# WiFi_Lock.net
KiCad netlist of a schematic drawn in Altium Designer
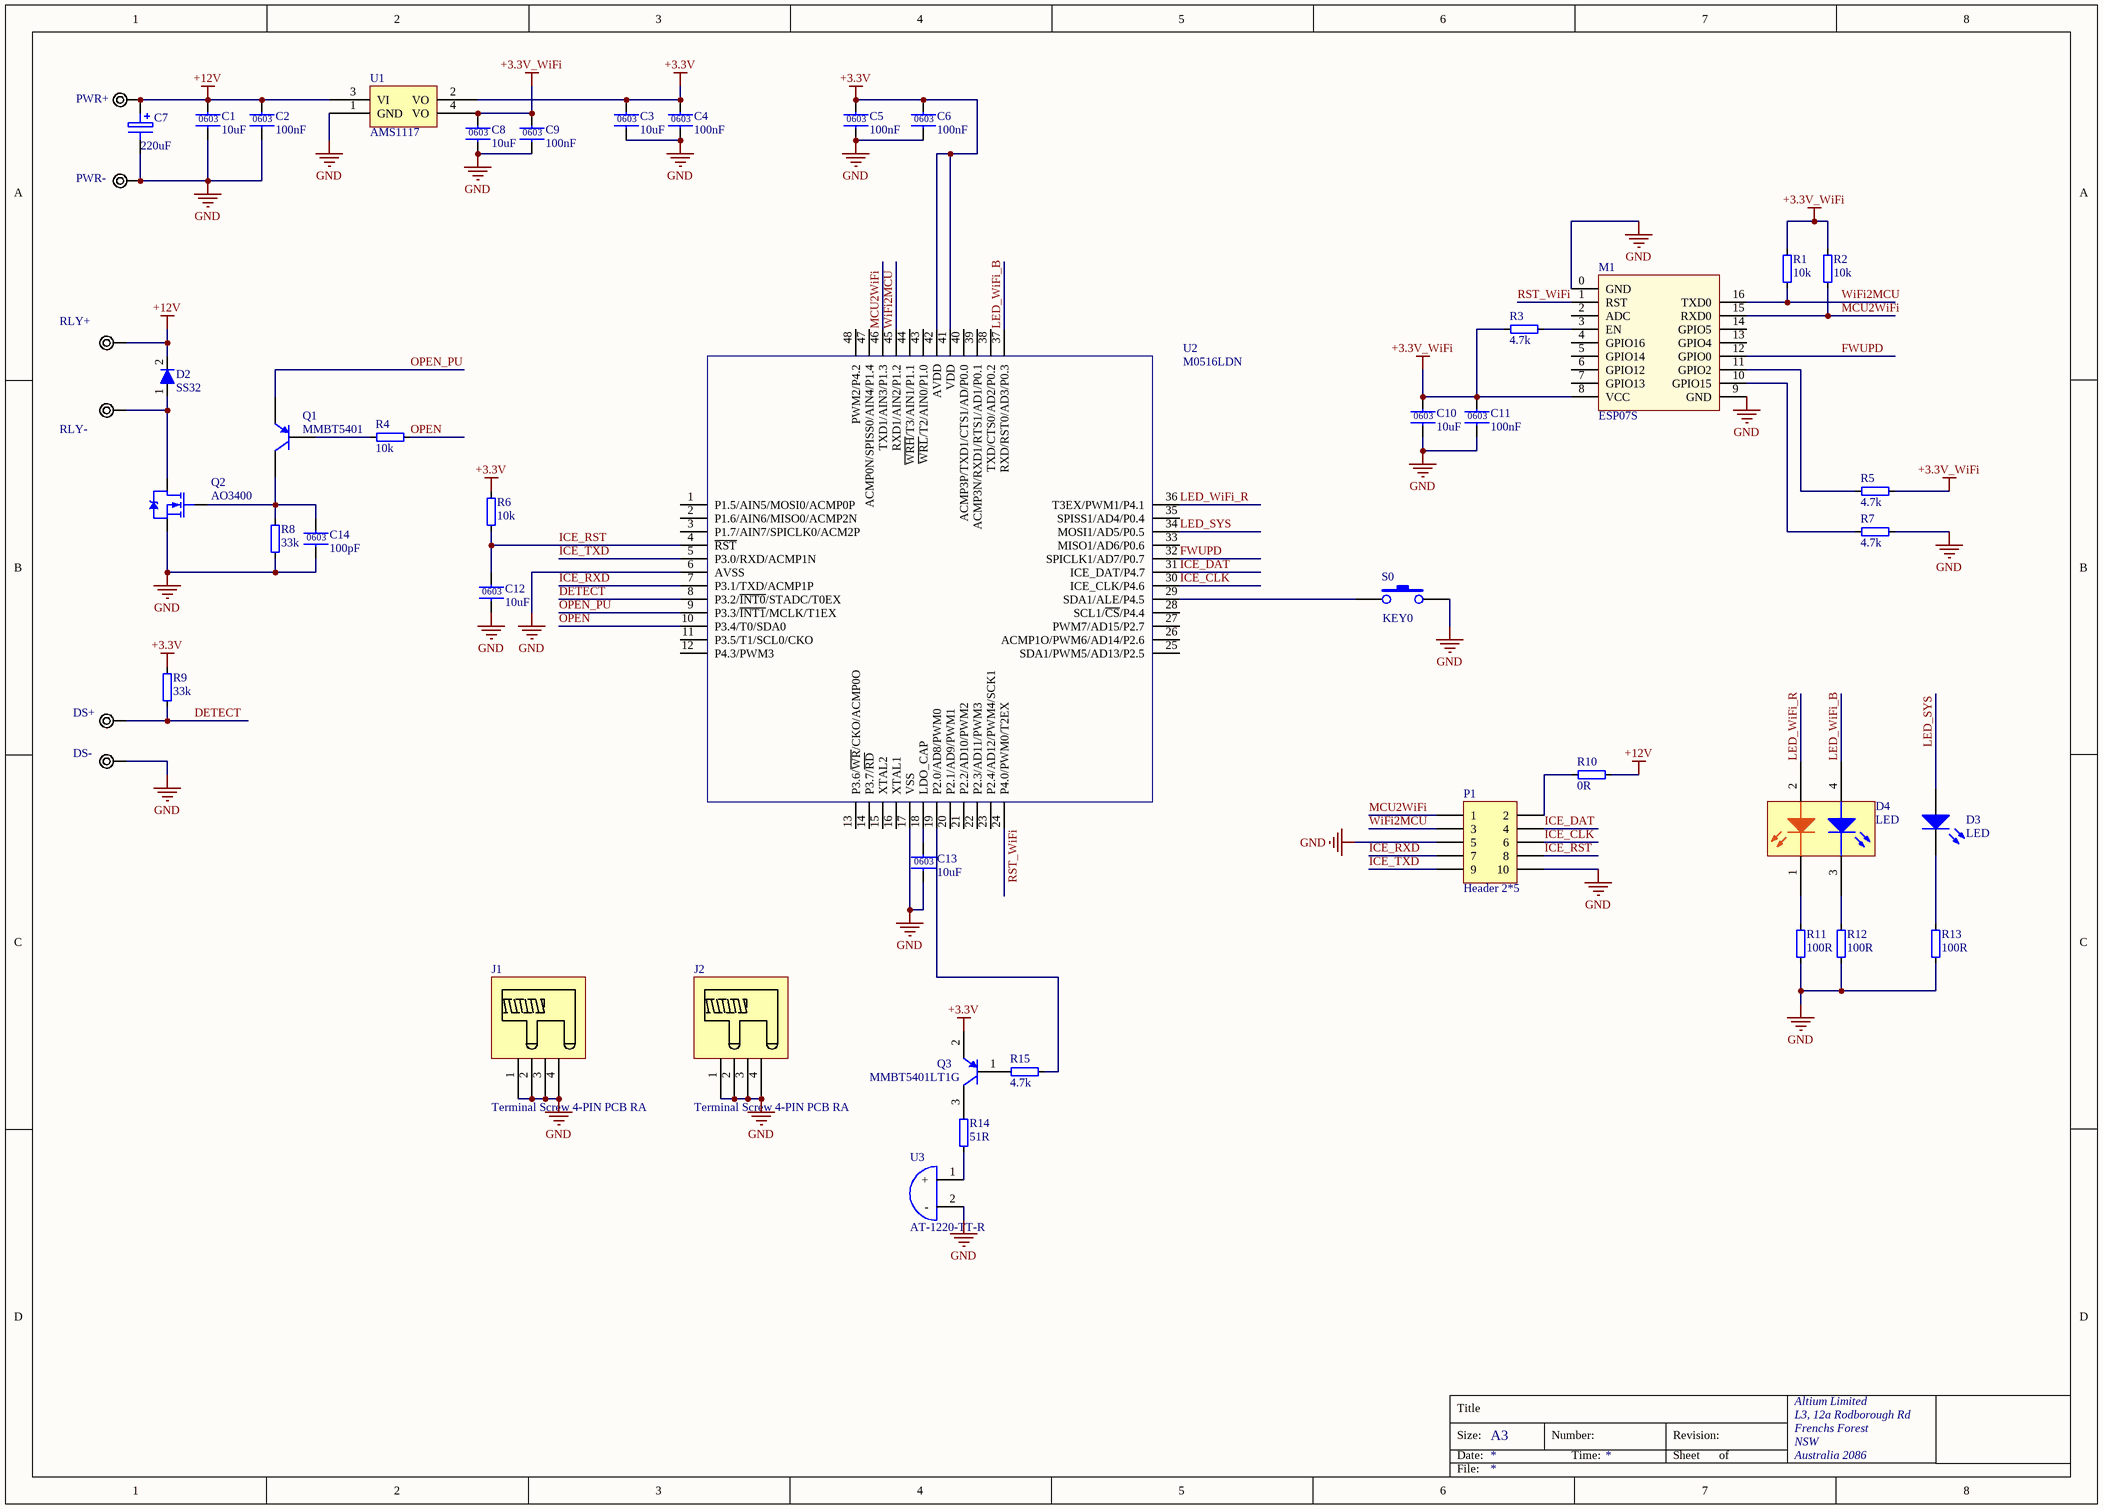
[diagram p0: WiFi_Lock.SchDoc]

(export (version "E")
  (design (tool "Eeschema 10.0.6"))
  (components
    (comp (ref "C1")
      (value "10uF")
      (footprint "0603")
      (description "CAP0603")
      (libsource (lib "AltiumDesignerIntLib") (part "CAP0603"))
    )
    (comp (ref "C2")
      (value "100nF")
      (footprint "0603")
      (description "CAP0603")
      (libsource (lib "AltiumDesignerIntLib") (part "CAP0603"))
    )
    (comp (ref "C3")
      (value "10uF")
      (footprint "0603")
      (description "CAP0603")
      (libsource (lib "AltiumDesignerIntLib") (part "CAP0603"))
    )
    (comp (ref "C4")
      (value "100nF")
      (footprint "0603")
      (description "CAP0603")
      (libsource (lib "AltiumDesignerIntLib") (part "CAP0603"))
    )
    (comp (ref "C5")
      (value "100nF")
      (footprint "0603")
      (description "CAP0603")
      (libsource (lib "AltiumDesignerIntLib") (part "CAP0603"))
    )
    (comp (ref "C6")
      (value "100nF")
      (footprint "0603")
      (description "CAP0603")
      (libsource (lib "AltiumDesignerIntLib") (part "CAP0603"))
    )
    (comp (ref "C7")
      (value "220uF")
      (footprint "SMD-EC-F6.3")
      (description "220μF 16V Aluminum Electrolytic Capacitors Radial, Can - SMD 160 mohm @ 100kHz 2000 Hrs @ 105°C")
      (fields
        (field (name "MANUFACTURER") "Panasonic Electronic Components")
        (field (name "PARTNUMBER") "EEE-FPC221XAP")
      )
      (libsource (lib "Panasonic Aluminum Electrolytic Capacitors (Surface Mount Type)") (part "EEE-FPC221XAP"))
    )
    (comp (ref "C8")
      (value "10uF")
      (footprint "0603")
      (description "CAP0603")
      (libsource (lib "AltiumDesignerIntLib") (part "CAP0603"))
    )
    (comp (ref "C9")
      (value "100nF")
      (footprint "0603")
      (description "CAP0603")
      (libsource (lib "AltiumDesignerIntLib") (part "CAP0603"))
    )
    (comp (ref "C10")
      (value "10uF")
      (footprint "0603")
      (description "CAP0603")
      (libsource (lib "AltiumDesignerIntLib") (part "CAP0603"))
    )
    (comp (ref "C11")
      (value "100nF")
      (footprint "0603")
      (description "CAP0603")
      (libsource (lib "AltiumDesignerIntLib") (part "CAP0603"))
    )
    (comp (ref "C12")
      (value "10uF")
      (footprint "0603")
      (description "CAP0603")
      (libsource (lib "AltiumDesignerIntLib") (part "CAP0603"))
    )
    (comp (ref "C13")
      (value "10uF")
      (footprint "0603")
      (description "CAP0603")
      (libsource (lib "AltiumDesignerIntLib") (part "CAP0603"))
    )
    (comp (ref "C14")
      (value "100pF")
      (footprint "0603")
      (description "CAP0603")
      (libsource (lib "AltiumDesignerIntLib") (part "CAP0603"))
    )
    (comp (ref "D2")
      (value "SS32")
      (footprint "DO-214AC")
      (libsource (lib "AltiumDesignerIntLib") (part "Diode"))
    )
    (comp (ref "D3")
      (value "LED")
      (footprint "0603")
      (description "Typical INFRARED GaAs LED")
      (fields (field (name "PUBLISHER") "Altium Limited"))
      (libsource (lib "AltiumDesignerIntLib") (part "LED"))
    )
    (comp (ref "D4")
      (value "LED")
      (footprint "DLED2.00x1.25mm")
      (description "Red & Blue")
      (libsource (lib "AltiumDesignerIntLib") (part "LED-RB"))
    )
    (comp (ref "J1")
      (value "Terminal Screw 4-PIN PCB RA")
      (footprint "TERMSCREW4-B11.5X8.5X7.8mm/T5.0X7.5mm/RA")
      (description "Terminal Screw 4-PIN, Thru Hole, PCB Right Angle")
      (libsource (lib "AltiumDesignerIntLib") (part "Terminal Screw 4-PIN PCB RA"))
    )
    (comp (ref "J2")
      (value "Terminal Screw 4-PIN PCB RA")
      (footprint "TERMSCREW4-B11.5X8.5X7.8mm/T5.0X7.5mm/RA")
      (description "Terminal Screw 4-PIN, Thru Hole, PCB Right Angle")
      (libsource (lib "AltiumDesignerIntLib") (part "Terminal Screw 4-PIN PCB RA"))
    )
    (comp (ref "M1")
      (value "ESP07S")
      (footprint "ESP-07S Module")
      (description "ESP-07S Wi-Fi Module")
      (libsource (lib "AltiumDesignerIntLib") (part "ESP-07S Module"))
    )
    (comp (ref "P1")
      (value "Header 2*5")
      (footprint "HDR2X5T0.1")
      (description "Header, 2-Pin, Dual row")
      (fields (field (name "PUBLISHER") "Altium Limited"))
      (libsource (lib "AltiumDesignerIntLib") (part "Header 2*5"))
    )
    (comp (ref "PAD1")
      (value "PWR+")
      (footprint "PAD-MUL-ROUND-D1.5H0.6")
      (description "Probe, Test Point")
      (libsource (lib "AltiumDesignerIntLib") (part "PAD"))
    )
    (comp (ref "PAD2")
      (value "PWR-")
      (footprint "PAD-MUL-ROUND-D1.5H0.6")
      (description "Probe, Test Point")
      (libsource (lib "AltiumDesignerIntLib") (part "PAD"))
    )
    (comp (ref "PAD3")
      (value "RLY+")
      (footprint "PAD-MUL-ROUND-D1.5H0.6")
      (description "Probe, Test Point")
      (libsource (lib "AltiumDesignerIntLib") (part "PAD"))
    )
    (comp (ref "PAD4")
      (value "RLY-")
      (footprint "PAD-MUL-ROUND-D1.5H0.6")
      (description "Probe, Test Point")
      (libsource (lib "AltiumDesignerIntLib") (part "PAD"))
    )
    (comp (ref "PAD5")
      (value "DS+")
      (footprint "PAD-MUL-ROUND-D1.5H0.6")
      (description "Probe, Test Point")
      (libsource (lib "AltiumDesignerIntLib") (part "PAD"))
    )
    (comp (ref "PAD6")
      (value "DS-")
      (footprint "PAD-MUL-ROUND-D1.5H0.6")
      (description "Probe, Test Point")
      (libsource (lib "AltiumDesignerIntLib") (part "PAD"))
    )
    (comp (ref "Q1")
      (value "MMBT5401")
      (footprint "SOT95P230X110-3N")
      (description "PNP General Purpose Amplifier")
      (libsource (lib "AltiumDesignerIntLib") (part "MMBT5401"))
    )
    (comp (ref "Q2")
      (value "AO3400")
      (footprint "SOT95P230X110-3N")
      (description "30V 5.8A N-Channel MOSFET, MAX VGS = 1.45V")
      (libsource (lib "AltiumDesignerIntLib") (part "AO3400"))
    )
    (comp (ref "Q3")
      (value "MMBT5401LT1G")
      (footprint "ONSC-SOT-23-3-318-08_V")
      (description "High Voltage Transistor, PNP Silicon, 3-Pin SOT-23, Pb-Free, Tape and Reel")
      (fields (field (name "MANUFACTURER") "On Semiconductor"))
      (libsource (lib "ON Semi General Purpose Transistors") (part "MMBT5401LT1G"))
    )
    (comp (ref "R1") (value "10k") (footprint "0603") (libsource (lib "AltiumDesignerIntLib") (part "RES")))
    (comp (ref "R2") (value "10k") (footprint "0603") (libsource (lib "AltiumDesignerIntLib") (part "RES")))
    (comp (ref "R3") (value "4.7k") (footprint "0603") (libsource (lib "AltiumDesignerIntLib") (part "RES")))
    (comp (ref "R4") (value "10k") (footprint "0603") (libsource (lib "AltiumDesignerIntLib") (part "RES")))
    (comp (ref "R5") (value "4.7k") (footprint "0603") (libsource (lib "AltiumDesignerIntLib") (part "RES")))
    (comp (ref "R6") (value "10k") (footprint "0603") (libsource (lib "AltiumDesignerIntLib") (part "RES")))
    (comp (ref "R7") (value "4.7k") (footprint "0603") (libsource (lib "AltiumDesignerIntLib") (part "RES")))
    (comp (ref "R8") (value "33k") (footprint "0603") (libsource (lib "AltiumDesignerIntLib") (part "RES")))
    (comp (ref "R9") (value "33k") (footprint "0603") (libsource (lib "AltiumDesignerIntLib") (part "RES")))
    (comp (ref "R10") (value "0R") (footprint "0603") (libsource (lib "AltiumDesignerIntLib") (part "RES")))
    (comp (ref "R11") (value "100R") (footprint "0603") (libsource (lib "AltiumDesignerIntLib") (part "RES")))
    (comp (ref "R12") (value "100R") (footprint "0603") (libsource (lib "AltiumDesignerIntLib") (part "RES")))
    (comp (ref "R13") (value "100R") (footprint "0603") (libsource (lib "AltiumDesignerIntLib") (part "RES")))
    (comp (ref "R14") (value "51R") (footprint "0603") (libsource (lib "AltiumDesignerIntLib") (part "RES")))
    (comp (ref "R15") (value "4.7k") (footprint "0603") (libsource (lib "AltiumDesignerIntLib") (part "RES")))
    (comp (ref "S0")
      (value "KEY0")
      (footprint "SW6.00x3.00mm")
      (description "Top push Switch")
      (libsource (lib "AltiumDesignerIntLib") (part "SW-TACT"))
    )
    (comp (ref "U1")
      (value "AMS1117")
      (footprint "SOT-223")
      (description "三端线性稳压")
      (libsource (lib "AltiumDesignerIntLib") (part "AMS1117"))
    )
    (comp (ref "U2")
      (value "M0516LDN")
      (footprint "LQFP-48")
      (description "ARM Cortex -M0 32-bit Microcontroller")
      (libsource (lib "AltiumDesignerIntLib") (part "M0516LDN"))
    )
    (comp (ref "U3")
      (value "AT-1220-TT-R")
      (footprint "Transducer_12mm(D)x8.5mm(H)_6.5mm(P)")
      (fields (field (name "MANUFACTURER") "PUI Audio Inc."))
      (libsource (lib "PUI Audio Transducers") (part "AT-1220-TT-R"))
    )
  )
  (nets
    (net (code "1") (name "+3.3V") (class "Default")
      (node (ref "C3") (pin "1") (pinfunction "1_1") (pintype "passive"))
      (node (ref "C4") (pin "1") (pinfunction "1_1") (pintype "passive"))
      (node (ref "C5") (pin "1") (pinfunction "1_1") (pintype "passive"))
      (node (ref "C6") (pin "1") (pinfunction "1_1") (pintype "passive"))
      (node (ref "Q3") (pin "2") (pinfunction "E_2") (pintype "passive"))
      (node (ref "R6") (pin "1") (pinfunction "1_1") (pintype "passive"))
      (node (ref "R9") (pin "2") (pinfunction "2_2") (pintype "passive"))
      (node (ref "U1") (pin "2") (pinfunction "VO_2") (pintype "passive"))
      (node (ref "U2") (pin "41") (pinfunction "VDD_41") (pintype "passive"))
      (node (ref "U2") (pin "42") (pinfunction "AVDD_42") (pintype "passive"))
    )
    (net (code "2") (name "+3.3V_WiFi") (class "Default")
      (node (ref "C10") (pin "1") (pinfunction "1_1") (pintype "passive"))
      (node (ref "C11") (pin "1") (pinfunction "1_1") (pintype "passive"))
      (node (ref "C8") (pin "1") (pinfunction "1_1") (pintype "passive"))
      (node (ref "C9") (pin "1") (pinfunction "1_1") (pintype "passive"))
      (node (ref "M1") (pin "8") (pinfunction "VCC_8") (pintype "passive"))
      (node (ref "R1") (pin "2") (pinfunction "2_2") (pintype "passive"))
      (node (ref "R2") (pin "2") (pinfunction "2_2") (pintype "passive"))
      (node (ref "R3") (pin "1") (pinfunction "1_1") (pintype "passive"))
      (node (ref "R5") (pin "2") (pinfunction "2_2") (pintype "passive"))
      (node (ref "U1") (pin "4") (pinfunction "VO_4") (pintype "passive"))
    )
    (net (code "3") (name "+12V") (class "Default")
      (node (ref "C1") (pin "1") (pinfunction "1_1") (pintype "passive"))
      (node (ref "C2") (pin "1") (pinfunction "1_1") (pintype "passive"))
      (node (ref "C7") (pin "1") (pinfunction "1_1") (pintype "passive"))
      (node (ref "D2") (pin "2") (pinfunction "K_2") (pintype "passive"))
      (node (ref "PAD1") (pin "1") (pinfunction "1_1") (pintype "passive"))
      (node (ref "PAD3") (pin "1") (pinfunction "1_1") (pintype "passive"))
      (node (ref "R10") (pin "2") (pinfunction "2_2") (pintype "passive"))
      (node (ref "U1") (pin "3") (pinfunction "VI_3") (pintype "passive"))
    )
    (net (code "4") (name "/DETECT") (class "Default")
      (node (ref "PAD5") (pin "1") (pinfunction "1_1") (pintype "passive"))
      (node (ref "R9") (pin "1") (pinfunction "1_1") (pintype "passive"))
      (node (ref "U2") (pin "8") (pinfunction "P3.2/~{INT0}/STADC/T0EX_8") (pintype "passive"))
    )
    (net (code "5") (name "/FWUPD") (class "Default")
      (node (ref "M1") (pin "12") (pinfunction "GPIO0_12") (pintype "passive"))
      (node (ref "U2") (pin "32") (pinfunction "SPICLK1/AD7/P0.7_32") (pintype "passive"))
    )
    (net (code "6") (name "/ICE_CLK") (class "Default")
      (node (ref "P1") (pin "6") (pinfunction "6_6") (pintype "passive"))
      (node (ref "U2") (pin "30") (pinfunction "ICE_CLK/P4.6_30") (pintype "passive"))
    )
    (net (code "7") (name "/ICE_DAT") (class "Default")
      (node (ref "P1") (pin "4") (pinfunction "4_4") (pintype "passive"))
      (node (ref "U2") (pin "31") (pinfunction "ICE_DAT/P4.7_31") (pintype "passive"))
    )
    (net (code "8") (name "/ICE_RST") (class "Default")
      (node (ref "C12") (pin "1") (pinfunction "1_1") (pintype "passive"))
      (node (ref "P1") (pin "8") (pinfunction "8_8") (pintype "passive"))
      (node (ref "R6") (pin "2") (pinfunction "2_2") (pintype "passive"))
      (node (ref "U2") (pin "4") (pinfunction "~{RST}_4") (pintype "passive"))
    )
    (net (code "9") (name "/ICE_RXD") (class "Default")
      (node (ref "P1") (pin "7") (pinfunction "7_7") (pintype "passive"))
      (node (ref "U2") (pin "7") (pinfunction "P3.1/TXD/ACMP1P_7") (pintype "passive"))
    )
    (net (code "10") (name "/ICE_TXD") (class "Default")
      (node (ref "P1") (pin "9") (pinfunction "9_9") (pintype "passive"))
      (node (ref "U2") (pin "5") (pinfunction "P3.0/RXD/ACMP1N_5") (pintype "passive"))
    )
    (net (code "11") (name "/LED_SYS") (class "Default")
      (node (ref "D3") (pin "1") (pinfunction "A_1") (pintype "passive"))
      (node (ref "U2") (pin "34") (pinfunction "MOSI1/AD5/P0.5_34") (pintype "passive"))
    )
    (net (code "12") (name "/LED_WiFi_B") (class "Default")
      (node (ref "D4") (pin "4") (pinfunction "BA_4") (pintype "passive"))
      (node (ref "U2") (pin "37") (pinfunction "RXD/RST0/AD3/P0.3_37") (pintype "passive"))
    )
    (net (code "13") (name "/LED_WiFi_R") (class "Default")
      (node (ref "D4") (pin "2") (pinfunction "RA_2") (pintype "passive"))
      (node (ref "U2") (pin "36") (pinfunction "T3EX/PWM1/P4.1_36") (pintype "passive"))
    )
    (net (code "14") (name "/MCU2WiFi") (class "Default")
      (node (ref "M1") (pin "15") (pinfunction "RXD0_15") (pintype "passive"))
      (node (ref "P1") (pin "1") (pinfunction "1_1") (pintype "passive"))
      (node (ref "R2") (pin "1") (pinfunction "1_1") (pintype "passive"))
      (node (ref "U2") (pin "46") (pinfunction "TXD1/AIN3/P1.3_46") (pintype "passive"))
    )
    (net (code "15") (name "/OPEN") (class "Default")
      (node (ref "R4") (pin "1") (pinfunction "1_1") (pintype "passive"))
      (node (ref "U2") (pin "10") (pinfunction "P3.4/T0/SDA0_10") (pintype "passive"))
    )
    (net (code "16") (name "/OPEN_PU") (class "Default")
      (node (ref "Q1") (pin "2") (pinfunction "E_2") (pintype "passive"))
      (node (ref "U2") (pin "9") (pinfunction "P3.3/~{INT1}/MCLK/T1EX_9") (pintype "passive"))
    )
    (net (code "17") (name "/RST_WiFi") (class "Default")
      (node (ref "M1") (pin "1") (pinfunction "RST_1") (pintype "passive"))
      (node (ref "U2") (pin "24") (pinfunction "P4.0/PWM0/T2EX_24") (pintype "passive"))
    )
    (net (code "18") (name "/WiFi2MCU") (class "Default")
      (node (ref "M1") (pin "16") (pinfunction "TXD0_16") (pintype "passive"))
      (node (ref "P1") (pin "3") (pinfunction "3_3") (pintype "passive"))
      (node (ref "R1") (pin "1") (pinfunction "1_1") (pintype "passive"))
      (node (ref "U2") (pin "45") (pinfunction "RXD1/AIN2/P1.2_45") (pintype "passive"))
    )
    (net (code "19") (name "GND") (class "Default")
      (node (ref "C1") (pin "2") (pinfunction "2_2") (pintype "passive"))
      (node (ref "C10") (pin "2") (pinfunction "2_2") (pintype "passive"))
      (node (ref "C11") (pin "2") (pinfunction "2_2") (pintype "passive"))
      (node (ref "C12") (pin "2") (pinfunction "2_2") (pintype "passive"))
      (node (ref "C13") (pin "2") (pinfunction "2_2") (pintype "passive"))
      (node (ref "C14") (pin "2") (pinfunction "2_2") (pintype "passive"))
      (node (ref "C2") (pin "2") (pinfunction "2_2") (pintype "passive"))
      (node (ref "C3") (pin "2") (pinfunction "2_2") (pintype "passive"))
      (node (ref "C4") (pin "2") (pinfunction "2_2") (pintype "passive"))
      (node (ref "C5") (pin "2") (pinfunction "2_2") (pintype "passive"))
      (node (ref "C6") (pin "2") (pinfunction "2_2") (pintype "passive"))
      (node (ref "C7") (pin "2") (pinfunction "2_2") (pintype "passive"))
      (node (ref "C8") (pin "2") (pinfunction "2_2") (pintype "passive"))
      (node (ref "C9") (pin "2") (pinfunction "2_2") (pintype "passive"))
      (node (ref "J1") (pin "1") (pintype "passive"))
      (node (ref "J1") (pin "2") (pintype "passive"))
      (node (ref "J1") (pin "3") (pintype "passive"))
      (node (ref "J1") (pin "4") (pintype "passive"))
      (node (ref "J2") (pin "1") (pintype "passive"))
      (node (ref "J2") (pin "2") (pintype "passive"))
      (node (ref "J2") (pin "3") (pintype "passive"))
      (node (ref "J2") (pin "4") (pintype "passive"))
      (node (ref "M1") (pin "0") (pinfunction "GND_0") (pintype "passive"))
      (node (ref "M1") (pin "9") (pinfunction "GND_9") (pintype "passive"))
      (node (ref "P1") (pin "10") (pinfunction "10_10") (pintype "passive"))
      (node (ref "P1") (pin "5") (pinfunction "5_5") (pintype "passive"))
      (node (ref "PAD2") (pin "1") (pinfunction "1_1") (pintype "passive"))
      (node (ref "PAD6") (pin "1") (pinfunction "1_1") (pintype "passive"))
      (node (ref "Q2") (pin "2") (pinfunction "S_2") (pintype "passive"))
      (node (ref "R11") (pin "1") (pinfunction "1_1") (pintype "passive"))
      (node (ref "R12") (pin "1") (pinfunction "1_1") (pintype "passive"))
      (node (ref "R13") (pin "1") (pinfunction "1_1") (pintype "passive"))
      (node (ref "R7") (pin "2") (pinfunction "2_2") (pintype "passive"))
      (node (ref "R8") (pin "1") (pinfunction "1_1") (pintype "passive"))
      (node (ref "S0") (pin "2") (pinfunction "2_2") (pintype "passive"))
      (node (ref "U1") (pin "1") (pinfunction "GND_1") (pintype "passive"))
      (node (ref "U2") (pin "17") (pinfunction "VSS_17") (pintype "passive"))
      (node (ref "U2") (pin "6") (pinfunction "AVSS_6") (pintype "passive"))
      (node (ref "U3") (pin "2") (pinfunction "-_2") (pintype "passive"))
    )
    (net (code "20") (name "Net-(D2-A)") (class "Default")
      (node (ref "D2") (pin "1") (pinfunction "A_1") (pintype "passive"))
      (node (ref "PAD4") (pin "1") (pinfunction "1_1") (pintype "passive"))
      (node (ref "Q2") (pin "3") (pinfunction "D_3") (pintype "passive"))
    )
    (net (code "21") (name "Net-(D3-K)") (class "Default")
      (node (ref "D3") (pin "2") (pinfunction "K_2") (pintype "passive"))
      (node (ref "R13") (pin "2") (pinfunction "2_2") (pintype "passive"))
    )
    (net (code "22") (name "Net-(D4-BK)") (class "Default")
      (node (ref "D4") (pin "3") (pinfunction "BK_3") (pintype "passive"))
      (node (ref "R12") (pin "2") (pinfunction "2_2") (pintype "passive"))
    )
    (net (code "23") (name "Net-(D4-RK)") (class "Default")
      (node (ref "D4") (pin "1") (pinfunction "RK_1") (pintype "passive"))
      (node (ref "R11") (pin "2") (pinfunction "2_2") (pintype "passive"))
    )
    (net (code "24") (name "Net-(M1-EN)") (class "Default")
      (node (ref "M1") (pin "3") (pinfunction "EN_3") (pintype "passive"))
      (node (ref "R3") (pin "2") (pinfunction "2_2") (pintype "passive"))
    )
    (net (code "25") (name "Net-(M1-GPIO2)") (class "Default")
      (node (ref "M1") (pin "11") (pinfunction "GPIO2_11") (pintype "passive"))
      (node (ref "R5") (pin "1") (pinfunction "1_1") (pintype "passive"))
    )
    (net (code "26") (name "Net-(M1-GPIO15)") (class "Default")
      (node (ref "M1") (pin "10") (pinfunction "GPIO15_10") (pintype "passive"))
      (node (ref "R7") (pin "1") (pinfunction "1_1") (pintype "passive"))
    )
    (net (code "27") (name "Net-(P1-Pad2)") (class "Default")
      (node (ref "P1") (pin "2") (pinfunction "2_2") (pintype "passive"))
      (node (ref "R10") (pin "1") (pinfunction "1_1") (pintype "passive"))
    )
    (net (code "28") (name "Net-(Q1-B)") (class "Default")
      (node (ref "Q1") (pin "1") (pinfunction "B_1") (pintype "passive"))
      (node (ref "R4") (pin "2") (pinfunction "2_2") (pintype "passive"))
    )
    (net (code "29") (name "Net-(Q1-C)") (class "Default")
      (node (ref "C14") (pin "1") (pinfunction "1_1") (pintype "passive"))
      (node (ref "Q1") (pin "3") (pinfunction "C_3") (pintype "passive"))
      (node (ref "Q2") (pin "1") (pinfunction "G_1") (pintype "passive"))
      (node (ref "R8") (pin "2") (pinfunction "2_2") (pintype "passive"))
    )
    (net (code "30") (name "Net-(Q3-B)") (class "Default")
      (node (ref "Q3") (pin "1") (pinfunction "B_1") (pintype "passive"))
      (node (ref "R15") (pin "1") (pinfunction "1_1") (pintype "passive"))
    )
    (net (code "31") (name "Net-(Q3-C)") (class "Default")
      (node (ref "Q3") (pin "3") (pinfunction "C_3") (pintype "passive"))
      (node (ref "R14") (pin "2") (pinfunction "2_2") (pintype "passive"))
    )
    (net (code "32") (name "Net-(U2-LDO_CAP)") (class "Default")
      (node (ref "C13") (pin "1") (pinfunction "1_1") (pintype "passive"))
      (node (ref "U2") (pin "18") (pinfunction "LDO_CAP_18") (pintype "passive"))
    )
    (net (code "33") (name "Net-(U2-P2.0{slash}AD8{slash}PWM0)") (class "Default")
      (node (ref "R15") (pin "2") (pinfunction "2_2") (pintype "passive"))
      (node (ref "U2") (pin "19") (pinfunction "P2.0/AD8/PWM0_19") (pintype "passive"))
    )
    (net (code "34") (name "Net-(U2-SDA1{slash}ALE{slash}P4.5)") (class "Default")
      (node (ref "S0") (pin "1") (pinfunction "1_1") (pintype "passive"))
      (node (ref "U2") (pin "29") (pinfunction "SDA1/ALE/P4.5_29") (pintype "passive"))
    )
    (net (code "35") (name "Net-(U3-+)") (class "Default")
      (node (ref "R14") (pin "1") (pinfunction "1_1") (pintype "passive"))
      (node (ref "U3") (pin "1") (pinfunction "+_1") (pintype "passive"))
    )
    (net (code "36") (name "unconnected-(M1-ADC-Pad2)") (class "Default")
      (node (ref "M1") (pin "2") (pinfunction "ADC_2") (pintype "passive"))
    )
    (net (code "37") (name "unconnected-(M1-GPIO4-Pad13)") (class "Default")
      (node (ref "M1") (pin "13") (pinfunction "GPIO4_13") (pintype "passive"))
    )
    (net (code "38") (name "unconnected-(M1-GPIO5-Pad14)") (class "Default")
      (node (ref "M1") (pin "14") (pinfunction "GPIO5_14") (pintype "passive"))
    )
    (net (code "39") (name "unconnected-(M1-GPIO12-Pad6)") (class "Default")
      (node (ref "M1") (pin "6") (pinfunction "GPIO12_6") (pintype "passive"))
    )
    (net (code "40") (name "unconnected-(M1-GPIO13-Pad7)") (class "Default")
      (node (ref "M1") (pin "7") (pinfunction "GPIO13_7") (pintype "passive"))
    )
    (net (code "41") (name "unconnected-(M1-GPIO14-Pad5)") (class "Default")
      (node (ref "M1") (pin "5") (pinfunction "GPIO14_5") (pintype "passive"))
    )
    (net (code "42") (name "unconnected-(M1-GPIO16-Pad4)") (class "Default")
      (node (ref "M1") (pin "4") (pinfunction "GPIO16_4") (pintype "passive"))
    )
    (net (code "43") (name "unconnected-(U2-ACMP0N{slash}SPISS0{slash}AIN4{slash}P1.4-Pad47)") (class "Default")
      (node (ref "U2") (pin "47") (pinfunction "ACMP0N/SPISS0/AIN4/P1.4_47") (pintype "passive"))
    )
    (net (code "44") (name "unconnected-(U2-ACMP1O{slash}PWM6{slash}AD14{slash}P2.6-Pad26)") (class "Default")
      (node (ref "U2") (pin "26") (pinfunction "ACMP1O/PWM6/AD14/P2.6_26") (pintype "passive"))
    )
    (net (code "45") (name "unconnected-(U2-ACMP3N{slash}RXD1{slash}RTS1{slash}AD1{slash}P0.1-Pad39)") (class "Default")
      (node (ref "U2") (pin "39") (pinfunction "ACMP3N/RXD1/RTS1/AD1/P0.1_39") (pintype "passive"))
    )
    (net (code "46") (name "unconnected-(U2-ACMP3P{slash}TXD1{slash}CTS1{slash}AD{slash}P0.0-Pad40)") (class "Default")
      (node (ref "U2") (pin "40") (pinfunction "ACMP3P/TXD1/CTS1/AD/P0.0_40") (pintype "passive"))
    )
    (net (code "47") (name "unconnected-(U2-MISO1{slash}AD6{slash}P0.6-Pad33)") (class "Default")
      (node (ref "U2") (pin "33") (pinfunction "MISO1/AD6/P0.6_33") (pintype "passive"))
    )
    (net (code "48") (name "unconnected-(U2-P1.5{slash}AIN5{slash}MOSI0{slash}ACMP0P-Pad1)") (class "Default")
      (node (ref "U2") (pin "1") (pinfunction "P1.5/AIN5/MOSI0/ACMP0P_1") (pintype "passive"))
    )
    (net (code "49") (name "unconnected-(U2-P1.6{slash}AIN6{slash}MISO0{slash}ACMP2N-Pad2)") (class "Default")
      (node (ref "U2") (pin "2") (pinfunction "P1.6/AIN6/MISO0/ACMP2N_2") (pintype "passive"))
    )
    (net (code "50") (name "unconnected-(U2-P1.7{slash}AIN7{slash}SPICLK0{slash}ACM2P-Pad3)") (class "Default")
      (node (ref "U2") (pin "3") (pinfunction "P1.7/AIN7/SPICLK0/ACM2P_3") (pintype "passive"))
    )
    (net (code "51") (name "unconnected-(U2-P2.1{slash}AD9{slash}PWM1-Pad20)") (class "Default")
      (node (ref "U2") (pin "20") (pinfunction "P2.1/AD9/PWM1_20") (pintype "passive"))
    )
    (net (code "52") (name "unconnected-(U2-P2.2{slash}AD10{slash}PWM2-Pad21)") (class "Default")
      (node (ref "U2") (pin "21") (pinfunction "P2.2/AD10/PWM2_21") (pintype "passive"))
    )
    (net (code "53") (name "unconnected-(U2-P2.3{slash}AD11{slash}PWM3-Pad22)") (class "Default")
      (node (ref "U2") (pin "22") (pinfunction "P2.3/AD11/PWM3_22") (pintype "passive"))
    )
    (net (code "54") (name "unconnected-(U2-P2.4{slash}AD12{slash}PWM4{slash}SCK1-Pad23)") (class "Default")
      (node (ref "U2") (pin "23") (pinfunction "P2.4/AD12/PWM4/SCK1_23") (pintype "passive"))
    )
    (net (code "55") (name "unconnected-(U2-P3.5{slash}T1{slash}SCL0{slash}CKO-Pad11)") (class "Default")
      (node (ref "U2") (pin "11") (pinfunction "P3.5/T1/SCL0/CKO_11") (pintype "passive"))
    )
    (net (code "56") (name "unconnected-(U2-P3.6{slash}~{WR}{slash}CKO{slash}ACMP0O-Pad13)") (class "Default")
      (node (ref "U2") (pin "13") (pinfunction "P3.6/~{WR}/CKO/ACMP0O_13") (pintype "passive"))
    )
    (net (code "57") (name "unconnected-(U2-P3.7{slash}~{RD}-Pad14)") (class "Default")
      (node (ref "U2") (pin "14") (pinfunction "P3.7/~{RD}_14") (pintype "passive"))
    )
    (net (code "58") (name "unconnected-(U2-P4.3{slash}PWM3-Pad12)") (class "Default")
      (node (ref "U2") (pin "12") (pinfunction "P4.3/PWM3_12") (pintype "passive"))
    )
    (net (code "59") (name "unconnected-(U2-PWM2{slash}P4.2-Pad48)") (class "Default")
      (node (ref "U2") (pin "48") (pinfunction "PWM2/P4.2_48") (pintype "passive"))
    )
    (net (code "60") (name "unconnected-(U2-PWM7{slash}AD15{slash}P2.7-Pad27)") (class "Default")
      (node (ref "U2") (pin "27") (pinfunction "PWM7/AD15/P2.7_27") (pintype "passive"))
    )
    (net (code "61") (name "unconnected-(U2-SCL1{slash}~{CS}{slash}P4.4-Pad28)") (class "Default")
      (node (ref "U2") (pin "28") (pinfunction "SCL1/~{CS}/P4.4_28") (pintype "passive"))
    )
    (net (code "62") (name "unconnected-(U2-SDA1{slash}PWM5{slash}AD13{slash}P2.5-Pad25)") (class "Default")
      (node (ref "U2") (pin "25") (pinfunction "SDA1/PWM5/AD13/P2.5_25") (pintype "passive"))
    )
    (net (code "63") (name "unconnected-(U2-SPISS1{slash}AD4{slash}P0.4-Pad35)") (class "Default")
      (node (ref "U2") (pin "35") (pinfunction "SPISS1/AD4/P0.4_35") (pintype "passive"))
    )
    (net (code "64") (name "unconnected-(U2-TXD{slash}CTS0{slash}AD2{slash}P0.2-Pad38)") (class "Default")
      (node (ref "U2") (pin "38") (pinfunction "TXD/CTS0/AD2/P0.2_38") (pintype "passive"))
    )
    (net (code "65") (name "unconnected-(U2-XTAL1-Pad16)") (class "Default")
      (node (ref "U2") (pin "16") (pinfunction "XTAL1_16") (pintype "passive"))
    )
    (net (code "66") (name "unconnected-(U2-XTAL2-Pad15)") (class "Default")
      (node (ref "U2") (pin "15") (pinfunction "XTAL2_15") (pintype "passive"))
    )
    (net (code "67") (name "unconnected-(U2-~{WRH}{slash}T3{slash}AIN1{slash}P1.1-Pad44)") (class "Default")
      (node (ref "U2") (pin "44") (pinfunction "~{WRH}/T3/AIN1/P1.1_44") (pintype "passive"))
    )
    (net (code "68") (name "unconnected-(U2-~{WRL}{slash}T2{slash}AIN0{slash}P1.0-Pad43)") (class "Default")
      (node (ref "U2") (pin "43") (pinfunction "~{WRL}/T2/AIN0/P1.0_43") (pintype "passive"))
    )
  )
)
